# Minsys8051V3.net
KiCad netlist of a schematic drawn in EAGLE
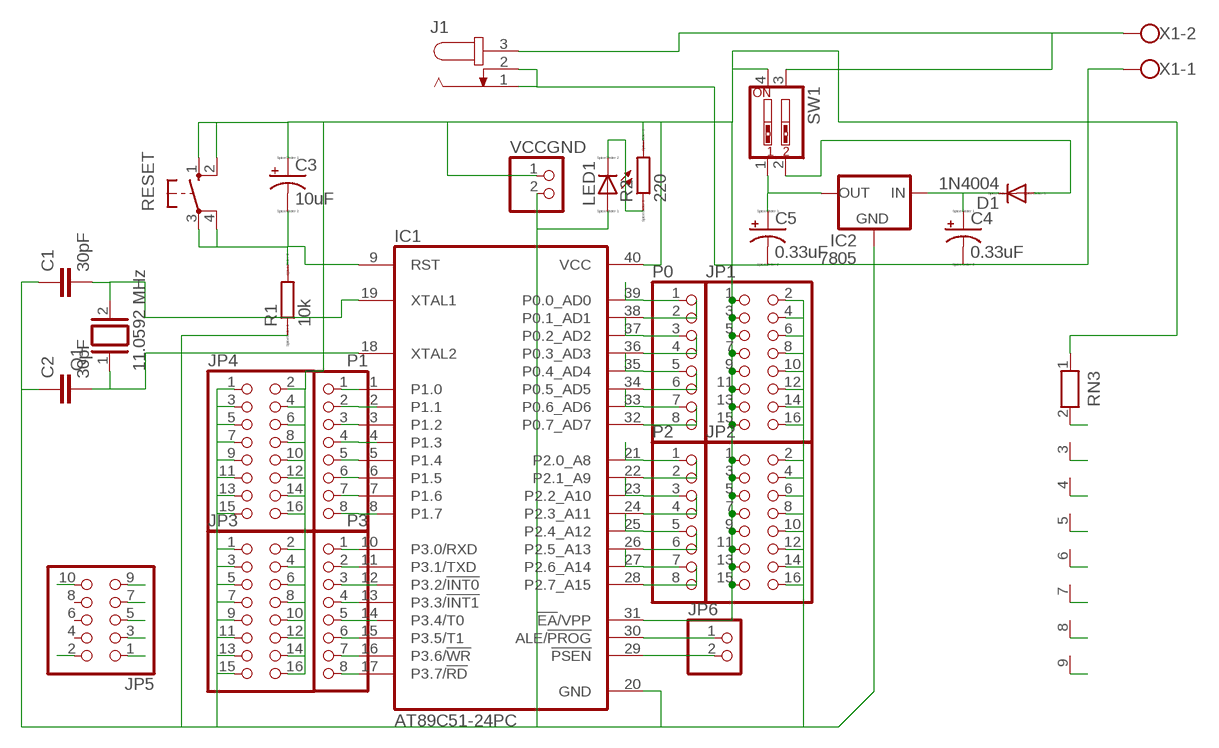
[diagram p0: schematic, sheet 1]

(export (version "E")
  (design (tool "Eeschema 10.0.6"))
  (components
    (comp (ref "C1")
      (value "30pF")
      (footprint "eagle-import:C025-025X050")
      (libsource (lib "eagle-import") (part "C-EU025-025X050"))
    )
    (comp (ref "C2")
      (value "30pF")
      (footprint "eagle-import:C025-025X050")
      (libsource (lib "eagle-import") (part "C-EU025-025X050"))
    )
    (comp (ref "C3")
      (value "10uF")
      (footprint "eagle-import:TT5D6")
      (libsource (lib "eagle-import") (part "CPOL-USTT6D6"))
    )
    (comp (ref "C4")
      (value "0.33uF")
      (footprint "eagle-import:TT5D6")
      (libsource (lib "eagle-import") (part "CPOL-USTT6D6"))
    )
    (comp (ref "C5")
      (value "0.33uF")
      (footprint "eagle-import:TT5D6")
      (libsource (lib "eagle-import") (part "CPOL-USTT6D6"))
    )
    (comp (ref "D1")
      (value "1N4004")
      (footprint "eagle-import:DO41-10")
      (libsource (lib "eagle-import") (part "1N4004"))
    )
    (comp (ref "IC1")
      (value "AT89C51-24PC")
      (footprint "eagle-import:DIL40")
      (libsource (lib "eagle-import") (part "AT89C51-PC24"))
    )
    (comp (ref "IC2")
      (value "7805")
      (footprint "eagle-import:78XXS")
      (libsource (lib "eagle-import") (part "78XXS"))
    )
    (comp (ref "J1")
      (value "JACK-PLUG1")
      (footprint "eagle-import:SPC4078")
      (libsource (lib "eagle-import") (part "JACK-PLUG1"))
    )
    (comp (ref "JP1")
      (value "PINHD-2X8")
      (footprint "eagle-import:2X08")
      (libsource (lib "eagle-import") (part "PINHD-2X8"))
    )
    (comp (ref "JP2")
      (value "PINHD-2X8")
      (footprint "eagle-import:2X08")
      (libsource (lib "eagle-import") (part "PINHD-2X8"))
    )
    (comp (ref "JP3")
      (value "PINHD-2X8")
      (footprint "eagle-import:2X08")
      (libsource (lib "eagle-import") (part "PINHD-2X8"))
    )
    (comp (ref "JP4")
      (value "PINHD-2X8")
      (footprint "eagle-import:2X08")
      (libsource (lib "eagle-import") (part "PINHD-2X8"))
    )
    (comp (ref "JP5")
      (value "PINHD-2X5")
      (footprint "eagle-import:2X05")
      (libsource (lib "eagle-import") (part "PINHD-2X5"))
    )
    (comp (ref "JP6")
      (value "PINHD-1X2")
      (footprint "eagle-import:1X02")
      (libsource (lib "eagle-import") (part "PINHD-1X2"))
    )
    (comp (ref "LED1")
      (value "LED_ELD260")
      (footprint "eagle-import:LED_LD260")
      (libsource (lib "eagle-import") (part "LED_ELD260"))
    )
    (comp (ref "P0")
      (value "PINHD-1X8")
      (footprint "eagle-import:1X08")
      (libsource (lib "eagle-import") (part "PINHD-1X8"))
    )
    (comp (ref "P1")
      (value "PINHD-1X8")
      (footprint "eagle-import:1X08")
      (libsource (lib "eagle-import") (part "PINHD-1X8"))
    )
    (comp (ref "P2")
      (value "PINHD-1X8")
      (footprint "eagle-import:1X08")
      (libsource (lib "eagle-import") (part "PINHD-1X8"))
    )
    (comp (ref "P3")
      (value "PINHD-1X8")
      (footprint "eagle-import:1X08")
      (libsource (lib "eagle-import") (part "PINHD-1X8"))
    )
    (comp (ref "Q1")
      (value "11.0592 MHz")
      (footprint "eagle-import:QS")
      (libsource (lib "eagle-import") (part "XTAL/S"))
    )
    (comp (ref "R1")
      (value "10k")
      (footprint "eagle-import:0207_10")
      (libsource (lib "eagle-import") (part "R0207/10"))
    )
    (comp (ref "R2")
      (value "220")
      (footprint "eagle-import:0207_10")
      (libsource (lib "eagle-import") (part "R0207/10"))
    )
    (comp (ref "RESET")
      (value "10-XX")
      (footprint "eagle-import:B3F-10XX")
      (fields (field (name "MPN") "B3F-1000"))
      (libsource (lib "eagle-import") (part "10-XX"))
    )
    (comp (ref "RN3")
      (value "RN08")
      (footprint "eagle-import:RN-9")
      (libsource (lib "eagle-import") (part "RN08"))
    )
    (comp (ref "SW1")
      (value "SW_DIP-2")
      (footprint "eagle-import:EDG-02")
      (libsource (lib "eagle-import") (part "SW_DIP-2"))
    )
    (comp (ref "VCCGND")
      (value "PINHD-1X2")
      (footprint "eagle-import:1X02")
      (libsource (lib "eagle-import") (part "PINHD-1X2"))
    )
    (comp (ref "X1")
      (value "W237-102")
      (footprint "eagle-import:W237-102")
      (fields (field (name "MPN") "237-102"))
      (libsource (lib "eagle-import") (part "W237-102"))
    )
  )
  (nets
    (net (code "1") (name "/GND") (class "Default")
      (node (ref "C1") (pin "1") (pinfunction "1_1") (pintype "passive"))
      (node (ref "C2") (pin "1") (pinfunction "1_1") (pintype "passive"))
      (node (ref "C4") (pin "-") (pinfunction "-_-") (pintype "passive"))
      (node (ref "C5") (pin "-") (pinfunction "-_-") (pintype "passive"))
      (node (ref "IC1") (pin "20") (pinfunction "GND_20") (pintype "power_in"))
      (node (ref "IC2") (pin "GND") (pinfunction "GND_GND") (pintype "input"))
      (node (ref "J1") (pin "1") (pinfunction "1_1") (pintype "passive"))
      (node (ref "J1") (pin "2") (pinfunction "2_2") (pintype "passive"))
      (node (ref "JP1") (pin "10") (pinfunction "10_10") (pintype "passive"))
      (node (ref "JP1") (pin "12") (pinfunction "12_12") (pintype "passive"))
      (node (ref "JP1") (pin "14") (pinfunction "14_14") (pintype "passive"))
      (node (ref "JP1") (pin "16") (pinfunction "16_16") (pintype "passive"))
      (node (ref "JP1") (pin "2") (pinfunction "2_2") (pintype "passive"))
      (node (ref "JP1") (pin "4") (pinfunction "4_4") (pintype "passive"))
      (node (ref "JP1") (pin "6") (pinfunction "6_6") (pintype "passive"))
      (node (ref "JP1") (pin "8") (pinfunction "8_8") (pintype "passive"))
      (node (ref "JP2") (pin "10") (pinfunction "10_10") (pintype "passive"))
      (node (ref "JP2") (pin "12") (pinfunction "12_12") (pintype "passive"))
      (node (ref "JP2") (pin "14") (pinfunction "14_14") (pintype "passive"))
      (node (ref "JP2") (pin "16") (pinfunction "16_16") (pintype "passive"))
      (node (ref "JP2") (pin "2") (pinfunction "2_2") (pintype "passive"))
      (node (ref "JP2") (pin "4") (pinfunction "4_4") (pintype "passive"))
      (node (ref "JP2") (pin "6") (pinfunction "6_6") (pintype "passive"))
      (node (ref "JP2") (pin "8") (pinfunction "8_8") (pintype "passive"))
      (node (ref "JP3") (pin "1") (pinfunction "1_1") (pintype "passive"))
      (node (ref "JP3") (pin "11") (pinfunction "11_11") (pintype "passive"))
      (node (ref "JP3") (pin "13") (pinfunction "13_13") (pintype "passive"))
      (node (ref "JP3") (pin "15") (pinfunction "15_15") (pintype "passive"))
      (node (ref "JP3") (pin "3") (pinfunction "3_3") (pintype "passive"))
      (node (ref "JP3") (pin "5") (pinfunction "5_5") (pintype "passive"))
      (node (ref "JP3") (pin "7") (pinfunction "7_7") (pintype "passive"))
      (node (ref "JP3") (pin "9") (pinfunction "9_9") (pintype "passive"))
      (node (ref "JP4") (pin "1") (pinfunction "1_1") (pintype "passive"))
      (node (ref "JP4") (pin "11") (pinfunction "11_11") (pintype "passive"))
      (node (ref "JP4") (pin "13") (pinfunction "13_13") (pintype "passive"))
      (node (ref "JP4") (pin "15") (pinfunction "15_15") (pintype "passive"))
      (node (ref "JP4") (pin "3") (pinfunction "3_3") (pintype "passive"))
      (node (ref "JP4") (pin "5") (pinfunction "5_5") (pintype "passive"))
      (node (ref "JP4") (pin "7") (pinfunction "7_7") (pintype "passive"))
      (node (ref "JP4") (pin "9") (pinfunction "9_9") (pintype "passive"))
      (node (ref "JP5") (pin "2") (pinfunction "2_2") (pintype "passive"))
      (node (ref "LED1") (pin "A") (pinfunction "A_A") (pintype "passive"))
      (node (ref "R1") (pin "1") (pinfunction "1_1") (pintype "passive"))
      (node (ref "VCCGND") (pin "2") (pinfunction "2_2") (pintype "passive"))
      (node (ref "X1") (pin "1") (pinfunction "KL_1") (pintype "passive"))
    )
    (net (code "2") (name "/MISO") (class "Default")
      (node (ref "IC1") (pin "7") (pinfunction "P1.6_7") (pintype "bidirectional"))
      (node (ref "JP5") (pin "1") (pinfunction "1_1") (pintype "passive"))
      (node (ref "P1") (pin "7") (pinfunction "7_7") (pintype "passive"))
    )
    (net (code "3") (name "/MOSI") (class "Default")
      (node (ref "IC1") (pin "6") (pinfunction "P1.5_6") (pintype "bidirectional"))
      (node (ref "JP5") (pin "9") (pinfunction "9_9") (pintype "passive"))
      (node (ref "P1") (pin "6") (pinfunction "6_6") (pintype "passive"))
    )
    (net (code "4") (name "/P00") (class "Default")
      (node (ref "IC1") (pin "39") (pinfunction "P0.0_AD0_39") (pintype "bidirectional"))
      (node (ref "P0") (pin "1") (pinfunction "1_1") (pintype "passive"))
      (node (ref "RN3") (pin "2") (pinfunction "2_2") (pintype "passive"))
    )
    (net (code "5") (name "/P01") (class "Default")
      (node (ref "IC1") (pin "38") (pinfunction "P0.1_AD1_38") (pintype "bidirectional"))
      (node (ref "P0") (pin "2") (pinfunction "2_2") (pintype "passive"))
      (node (ref "RN3") (pin "3") (pinfunction "3_3") (pintype "passive"))
    )
    (net (code "6") (name "/P02") (class "Default")
      (node (ref "IC1") (pin "37") (pinfunction "P0.2_AD2_37") (pintype "bidirectional"))
      (node (ref "P0") (pin "3") (pinfunction "3_3") (pintype "passive"))
      (node (ref "RN3") (pin "4") (pinfunction "4_4") (pintype "passive"))
    )
    (net (code "7") (name "/P03") (class "Default")
      (node (ref "IC1") (pin "36") (pinfunction "P0.3_AD3_36") (pintype "bidirectional"))
      (node (ref "P0") (pin "4") (pinfunction "4_4") (pintype "passive"))
      (node (ref "RN3") (pin "5") (pinfunction "5_5") (pintype "passive"))
    )
    (net (code "8") (name "/P04") (class "Default")
      (node (ref "IC1") (pin "35") (pinfunction "P0.4_AD4_35") (pintype "bidirectional"))
      (node (ref "P0") (pin "5") (pinfunction "5_5") (pintype "passive"))
      (node (ref "RN3") (pin "6") (pinfunction "6_6") (pintype "passive"))
    )
    (net (code "9") (name "/P05") (class "Default")
      (node (ref "IC1") (pin "34") (pinfunction "P0.5_AD5_34") (pintype "bidirectional"))
      (node (ref "P0") (pin "6") (pinfunction "6_6") (pintype "passive"))
      (node (ref "RN3") (pin "7") (pinfunction "7_7") (pintype "passive"))
    )
    (net (code "10") (name "/P06") (class "Default")
      (node (ref "IC1") (pin "33") (pinfunction "P0.6_AD6_33") (pintype "bidirectional"))
      (node (ref "P0") (pin "7") (pinfunction "7_7") (pintype "passive"))
      (node (ref "RN3") (pin "8") (pinfunction "8_8") (pintype "passive"))
    )
    (net (code "11") (name "/P07") (class "Default")
      (node (ref "IC1") (pin "32") (pinfunction "P0.7_AD7_32") (pintype "bidirectional"))
      (node (ref "P0") (pin "8") (pinfunction "8_8") (pintype "passive"))
      (node (ref "RN3") (pin "9") (pinfunction "9_9") (pintype "passive"))
    )
    (net (code "12") (name "/RST") (class "Default")
      (node (ref "C3") (pin "-") (pinfunction "-_-") (pintype "passive"))
      (node (ref "IC1") (pin "9") (pinfunction "RST_9") (pintype "input"))
      (node (ref "JP5") (pin "5") (pinfunction "5_5") (pintype "passive"))
      (node (ref "R1") (pin "2") (pinfunction "2_2") (pintype "passive"))
      (node (ref "RESET") (pin "3") (pinfunction "P_3") (pintype "passive"))
      (node (ref "RESET") (pin "4") (pinfunction "P1_4") (pintype "passive"))
    )
    (net (code "13") (name "/SCK") (class "Default")
      (node (ref "IC1") (pin "8") (pinfunction "P1.7_8") (pintype "bidirectional"))
      (node (ref "JP5") (pin "3") (pinfunction "3_3") (pintype "passive"))
      (node (ref "P1") (pin "8") (pinfunction "8_8") (pintype "passive"))
    )
    (net (code "14") (name "/VCC") (class "Default")
      (node (ref "C3") (pin "+") (pinfunction "+_+") (pintype "passive"))
      (node (ref "IC1") (pin "31") (pinfunction "~{EA}/VPP_31") (pintype "input"))
      (node (ref "IC1") (pin "40") (pinfunction "VCC_40") (pintype "power_in"))
      (node (ref "JP1") (pin "1") (pinfunction "1_1") (pintype "passive"))
      (node (ref "JP1") (pin "11") (pinfunction "11_11") (pintype "passive"))
      (node (ref "JP1") (pin "13") (pinfunction "13_13") (pintype "passive"))
      (node (ref "JP1") (pin "15") (pinfunction "15_15") (pintype "passive"))
      (node (ref "JP1") (pin "3") (pinfunction "3_3") (pintype "passive"))
      (node (ref "JP1") (pin "5") (pinfunction "5_5") (pintype "passive"))
      (node (ref "JP1") (pin "7") (pinfunction "7_7") (pintype "passive"))
      (node (ref "JP1") (pin "9") (pinfunction "9_9") (pintype "passive"))
      (node (ref "JP2") (pin "1") (pinfunction "1_1") (pintype "passive"))
      (node (ref "JP2") (pin "11") (pinfunction "11_11") (pintype "passive"))
      (node (ref "JP2") (pin "13") (pinfunction "13_13") (pintype "passive"))
      (node (ref "JP2") (pin "15") (pinfunction "15_15") (pintype "passive"))
      (node (ref "JP2") (pin "3") (pinfunction "3_3") (pintype "passive"))
      (node (ref "JP2") (pin "5") (pinfunction "5_5") (pintype "passive"))
      (node (ref "JP2") (pin "7") (pinfunction "7_7") (pintype "passive"))
      (node (ref "JP2") (pin "9") (pinfunction "9_9") (pintype "passive"))
      (node (ref "JP3") (pin "10") (pinfunction "10_10") (pintype "passive"))
      (node (ref "JP3") (pin "12") (pinfunction "12_12") (pintype "passive"))
      (node (ref "JP3") (pin "14") (pinfunction "14_14") (pintype "passive"))
      (node (ref "JP3") (pin "16") (pinfunction "16_16") (pintype "passive"))
      (node (ref "JP3") (pin "2") (pinfunction "2_2") (pintype "passive"))
      (node (ref "JP3") (pin "4") (pinfunction "4_4") (pintype "passive"))
      (node (ref "JP3") (pin "6") (pinfunction "6_6") (pintype "passive"))
      (node (ref "JP3") (pin "8") (pinfunction "8_8") (pintype "passive"))
      (node (ref "JP4") (pin "10") (pinfunction "10_10") (pintype "passive"))
      (node (ref "JP4") (pin "12") (pinfunction "12_12") (pintype "passive"))
      (node (ref "JP4") (pin "14") (pinfunction "14_14") (pintype "passive"))
      (node (ref "JP4") (pin "16") (pinfunction "16_16") (pintype "passive"))
      (node (ref "JP4") (pin "2") (pinfunction "2_2") (pintype "passive"))
      (node (ref "JP4") (pin "4") (pinfunction "4_4") (pintype "passive"))
      (node (ref "JP4") (pin "6") (pinfunction "6_6") (pintype "passive"))
      (node (ref "JP4") (pin "8") (pinfunction "8_8") (pintype "passive"))
      (node (ref "JP5") (pin "10") (pinfunction "10_10") (pintype "passive"))
      (node (ref "R2") (pin "2") (pinfunction "2_2") (pintype "passive"))
      (node (ref "RESET") (pin "1") (pinfunction "S_1") (pintype "passive"))
      (node (ref "RESET") (pin "2") (pinfunction "S1_2") (pintype "passive"))
      (node (ref "RN3") (pin "1") (pinfunction "1_1") (pintype "passive"))
      (node (ref "SW1") (pin "4") (pinfunction "4_4") (pintype "passive"))
      (node (ref "VCCGND") (pin "1") (pinfunction "1_1") (pintype "passive"))
    )
    (net (code "15") (name "Net-(C4-Pad+)") (class "Default")
      (node (ref "C4") (pin "+") (pinfunction "+_+") (pintype "passive"))
      (node (ref "D1") (pin "C") (pinfunction "C_C") (pintype "passive"))
      (node (ref "IC2") (pin "IN") (pinfunction "IN_IN") (pintype "input"))
    )
    (net (code "16") (name "Net-(C5-Pad+)") (class "Default")
      (node (ref "C5") (pin "+") (pinfunction "+_+") (pintype "passive"))
      (node (ref "IC2") (pin "OUT") (pinfunction "OUT_OUT") (pintype "passive"))
      (node (ref "SW1") (pin "1") (pinfunction "1_1") (pintype "passive"))
    )
    (net (code "17") (name "Net-(D1-PadA)") (class "Default")
      (node (ref "D1") (pin "A") (pinfunction "A_A") (pintype "passive"))
      (node (ref "SW1") (pin "2") (pinfunction "2_2") (pintype "passive"))
    )
    (net (code "18") (name "Net-(IC1-ALE{slash}~{PROG})") (class "Default")
      (node (ref "IC1") (pin "30") (pinfunction "ALE/~{PROG}_30") (pintype "output"))
      (node (ref "JP6") (pin "1") (pinfunction "1_1") (pintype "passive"))
    )
    (net (code "19") (name "Net-(IC1-P1.0)") (class "Default")
      (node (ref "IC1") (pin "1") (pinfunction "P1.0_1") (pintype "bidirectional"))
      (node (ref "P1") (pin "1") (pinfunction "1_1") (pintype "passive"))
    )
    (net (code "20") (name "Net-(IC1-P1.1)") (class "Default")
      (node (ref "IC1") (pin "2") (pinfunction "P1.1_2") (pintype "bidirectional"))
      (node (ref "P1") (pin "2") (pinfunction "2_2") (pintype "passive"))
    )
    (net (code "21") (name "Net-(IC1-P1.2)") (class "Default")
      (node (ref "IC1") (pin "3") (pinfunction "P1.2_3") (pintype "bidirectional"))
      (node (ref "P1") (pin "3") (pinfunction "3_3") (pintype "passive"))
    )
    (net (code "22") (name "Net-(IC1-P1.3)") (class "Default")
      (node (ref "IC1") (pin "4") (pinfunction "P1.3_4") (pintype "bidirectional"))
      (node (ref "P1") (pin "4") (pinfunction "4_4") (pintype "passive"))
    )
    (net (code "23") (name "Net-(IC1-P1.4)") (class "Default")
      (node (ref "IC1") (pin "5") (pinfunction "P1.4_5") (pintype "bidirectional"))
      (node (ref "P1") (pin "5") (pinfunction "5_5") (pintype "passive"))
    )
    (net (code "24") (name "Net-(IC1-P2.0_A8)") (class "Default")
      (node (ref "IC1") (pin "21") (pinfunction "P2.0_A8_21") (pintype "bidirectional"))
      (node (ref "P2") (pin "1") (pinfunction "1_1") (pintype "passive"))
    )
    (net (code "25") (name "Net-(IC1-P2.1_A9)") (class "Default")
      (node (ref "IC1") (pin "22") (pinfunction "P2.1_A9_22") (pintype "bidirectional"))
      (node (ref "P2") (pin "2") (pinfunction "2_2") (pintype "passive"))
    )
    (net (code "26") (name "Net-(IC1-P2.2_A10)") (class "Default")
      (node (ref "IC1") (pin "23") (pinfunction "P2.2_A10_23") (pintype "bidirectional"))
      (node (ref "P2") (pin "3") (pinfunction "3_3") (pintype "passive"))
    )
    (net (code "27") (name "Net-(IC1-P2.3_A11)") (class "Default")
      (node (ref "IC1") (pin "24") (pinfunction "P2.3_A11_24") (pintype "bidirectional"))
      (node (ref "P2") (pin "4") (pinfunction "4_4") (pintype "passive"))
    )
    (net (code "28") (name "Net-(IC1-P2.4_A12)") (class "Default")
      (node (ref "IC1") (pin "25") (pinfunction "P2.4_A12_25") (pintype "bidirectional"))
      (node (ref "P2") (pin "5") (pinfunction "5_5") (pintype "passive"))
    )
    (net (code "29") (name "Net-(IC1-P2.5_A13)") (class "Default")
      (node (ref "IC1") (pin "26") (pinfunction "P2.5_A13_26") (pintype "bidirectional"))
      (node (ref "P2") (pin "6") (pinfunction "6_6") (pintype "passive"))
    )
    (net (code "30") (name "Net-(IC1-P2.6_A14)") (class "Default")
      (node (ref "IC1") (pin "27") (pinfunction "P2.6_A14_27") (pintype "bidirectional"))
      (node (ref "P2") (pin "7") (pinfunction "7_7") (pintype "passive"))
    )
    (net (code "31") (name "Net-(IC1-P2.7_A15)") (class "Default")
      (node (ref "IC1") (pin "28") (pinfunction "P2.7_A15_28") (pintype "bidirectional"))
      (node (ref "P2") (pin "8") (pinfunction "8_8") (pintype "passive"))
    )
    (net (code "32") (name "Net-(IC1-P3.0{slash}RXD)") (class "Default")
      (node (ref "IC1") (pin "10") (pinfunction "P3.0/RXD_10") (pintype "bidirectional"))
      (node (ref "P3") (pin "1") (pinfunction "1_1") (pintype "passive"))
    )
    (net (code "33") (name "Net-(IC1-P3.1{slash}TXD)") (class "Default")
      (node (ref "IC1") (pin "11") (pinfunction "P3.1/TXD_11") (pintype "bidirectional"))
      (node (ref "P3") (pin "2") (pinfunction "2_2") (pintype "passive"))
    )
    (net (code "34") (name "Net-(IC1-P3.2{slash}~{INT0})") (class "Default")
      (node (ref "IC1") (pin "12") (pinfunction "P3.2/~{INT0}_12") (pintype "bidirectional"))
      (node (ref "P3") (pin "3") (pinfunction "3_3") (pintype "passive"))
    )
    (net (code "35") (name "Net-(IC1-P3.3{slash}~{INT1})") (class "Default")
      (node (ref "IC1") (pin "13") (pinfunction "P3.3/~{INT1}_13") (pintype "bidirectional"))
      (node (ref "P3") (pin "4") (pinfunction "4_4") (pintype "passive"))
    )
    (net (code "36") (name "Net-(IC1-P3.4{slash}T0)") (class "Default")
      (node (ref "IC1") (pin "14") (pinfunction "P3.4/T0_14") (pintype "bidirectional"))
      (node (ref "P3") (pin "5") (pinfunction "5_5") (pintype "passive"))
    )
    (net (code "37") (name "Net-(IC1-P3.5{slash}T1)") (class "Default")
      (node (ref "IC1") (pin "15") (pinfunction "P3.5/T1_15") (pintype "bidirectional"))
      (node (ref "P3") (pin "6") (pinfunction "6_6") (pintype "passive"))
    )
    (net (code "38") (name "Net-(IC1-P3.6{slash}~{WR})") (class "Default")
      (node (ref "IC1") (pin "16") (pinfunction "P3.6/~{WR}_16") (pintype "bidirectional"))
      (node (ref "P3") (pin "7") (pinfunction "7_7") (pintype "passive"))
    )
    (net (code "39") (name "Net-(IC1-P3.7{slash}~{RD})") (class "Default")
      (node (ref "IC1") (pin "17") (pinfunction "P3.7/~{RD}_17") (pintype "bidirectional"))
      (node (ref "P3") (pin "8") (pinfunction "8_8") (pintype "passive"))
    )
    (net (code "40") (name "Net-(IC1-XTAL1)") (class "Default")
      (node (ref "C1") (pin "2") (pinfunction "2_2") (pintype "passive"))
      (node (ref "IC1") (pin "19") (pinfunction "XTAL1_19") (pintype "input"))
      (node (ref "Q1") (pin "2") (pinfunction "2_2") (pintype "passive"))
    )
    (net (code "41") (name "Net-(IC1-XTAL2)") (class "Default")
      (node (ref "C2") (pin "2") (pinfunction "2_2") (pintype "passive"))
      (node (ref "IC1") (pin "18") (pinfunction "XTAL2_18") (pintype "input"))
      (node (ref "Q1") (pin "1") (pinfunction "1_1") (pintype "passive"))
    )
    (net (code "42") (name "Net-(IC1-~{PSEN})") (class "Default")
      (node (ref "IC1") (pin "29") (pinfunction "~{PSEN}_29") (pintype "output"))
      (node (ref "JP6") (pin "2") (pinfunction "2_2") (pintype "passive"))
    )
    (net (code "43") (name "Net-(LED1-C)") (class "Default")
      (node (ref "LED1") (pin "K") (pinfunction "C_K") (pintype "passive"))
      (node (ref "R2") (pin "1") (pinfunction "1_1") (pintype "passive"))
    )
    (net (code "44") (name "Net-(X1B-KL)") (class "Default")
      (node (ref "J1") (pin "3") (pinfunction "3_3") (pintype "passive"))
      (node (ref "SW1") (pin "3") (pinfunction "3_3") (pintype "passive"))
      (node (ref "X1") (pin "2") (pinfunction "KL_2") (pintype "passive"))
    )
    (net (code "45") (name "unconnected-(JP5-Pad4)") (class "Default")
      (node (ref "JP5") (pin "4") (pinfunction "4_4") (pintype "passive"))
    )
    (net (code "46") (name "unconnected-(JP5-Pad6)") (class "Default")
      (node (ref "JP5") (pin "6") (pinfunction "6_6") (pintype "passive"))
    )
    (net (code "47") (name "unconnected-(JP5-Pad7)") (class "Default")
      (node (ref "JP5") (pin "7") (pinfunction "7_7") (pintype "passive"))
    )
    (net (code "48") (name "unconnected-(JP5-Pad8)") (class "Default")
      (node (ref "JP5") (pin "8") (pinfunction "8_8") (pintype "passive"))
    )
  )
)
